# Gesture.net
KiCad netlist of a schematic drawn in EAGLE
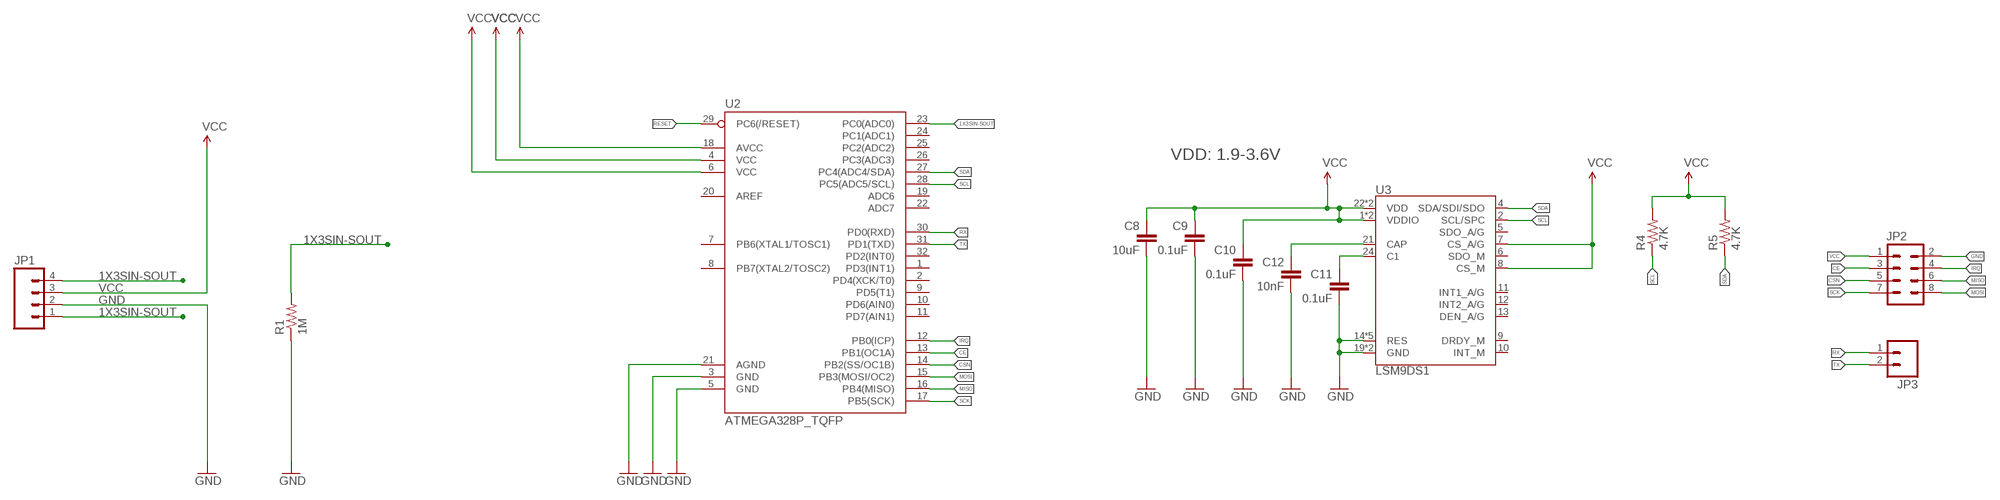
[diagram p0: schematic, sheet 1]

(export (version "E")
  (design (tool "Eeschema 10.0.6"))
  (components
    (comp (ref "C8")
      (value "10uF")
      (footprint "eagle-import:0603-CAP")
      (libsource (lib "eagle-import") (part "10UF-6.3V-20%(0603)"))
    )
    (comp (ref "C9")
      (value "0.1uF")
      (footprint "eagle-import:0603-CAP")
      (libsource (lib "eagle-import") (part "0.1UF-25V(+80/-20%)(0603)"))
    )
    (comp (ref "C10")
      (value "0.1uF")
      (footprint "eagle-import:0603-CAP")
      (libsource (lib "eagle-import") (part "0.1UF-25V(+80/-20%)(0603)"))
    )
    (comp (ref "C11")
      (value "0.1uF")
      (footprint "eagle-import:0603-CAP")
      (libsource (lib "eagle-import") (part "0.1UF-25V(+80/-20%)(0603)"))
    )
    (comp (ref "C12")
      (value "10nF")
      (footprint "eagle-import:0603-CAP")
      (libsource (lib "eagle-import") (part "10NF/10000PF-50V-10%(0603)"))
    )
    (comp (ref "JP1")
      (value "M04PTH")
      (footprint "eagle-import:1X04")
      (libsource (lib "eagle-import") (part "M04PTH"))
    )
    (comp (ref "JP2")
      (value "M04X2_0.05\"")
      (footprint "eagle-import:M04X2_0.05_")
      (libsource (lib "eagle-import") (part "M04X2_0.05{dblquote}"))
    )
    (comp (ref "JP3")
      (value "M02LOCK")
      (footprint "eagle-import:1X02_LOCK")
      (libsource (lib "eagle-import") (part "M02LOCK"))
    )
    (comp (ref "R1")
      (value "1M")
      (footprint "eagle-import:R0603")
      (libsource (lib "eagle-import") (part "R-US_R0603"))
    )
    (comp (ref "R4")
      (value "4.7K")
      (footprint "eagle-import:0603-RES")
      (libsource (lib "eagle-import") (part "4.7KOHM-1/10W-1%(0603)"))
    )
    (comp (ref "R5")
      (value "4.7K")
      (footprint "eagle-import:0603-RES")
      (libsource (lib "eagle-import") (part "4.7KOHM-1/10W-1%(0603)"))
    )
    (comp (ref "U2")
      (value "ATMEGA328P_TQFP")
      (footprint "eagle-import:TQFP32-08")
      (libsource (lib "eagle-import") (part "ATMEGA328P_TQFP"))
    )
    (comp (ref "U3")
      (value "LSM9DS1")
      (footprint "eagle-import:LGA24-8X4")
      (libsource (lib "eagle-import") (part "LSM9DS1"))
    )
  )
  (nets
    (net (code "1") (name "1X3SIN-SOUT") (class "Default")
      (node (ref "JP1") (pin "1") (pinfunction "1_1") (pintype "passive"))
      (node (ref "JP1") (pin "4") (pinfunction "4_4") (pintype "passive"))
      (node (ref "R1") (pin "2") (pinfunction "2_2") (pintype "passive"))
      (node (ref "U2") (pin "23") (pinfunction "PC0(ADC0)_23") (pintype "bidirectional"))
    )
    (net (code "2") (name "CE") (class "Default")
      (node (ref "JP2") (pin "3") (pinfunction "3_3") (pintype "passive"))
      (node (ref "U2") (pin "13") (pinfunction "PB1(OC1A)_13") (pintype "bidirectional"))
    )
    (net (code "3") (name "CSN") (class "Default")
      (node (ref "JP2") (pin "5") (pinfunction "5_5") (pintype "passive"))
      (node (ref "U2") (pin "14") (pinfunction "PB2(SS/OC1B)_14") (pintype "bidirectional"))
    )
    (net (code "4") (name "GND") (class "Default")
      (node (ref "C10") (pin "2") (pinfunction "2_2") (pintype "passive"))
      (node (ref "C11") (pin "2") (pinfunction "2_2") (pintype "passive"))
      (node (ref "C12") (pin "2") (pinfunction "2_2") (pintype "passive"))
      (node (ref "C8") (pin "2") (pinfunction "2_2") (pintype "passive"))
      (node (ref "C9") (pin "2") (pinfunction "2_2") (pintype "passive"))
      (node (ref "JP1") (pin "2") (pinfunction "2_2") (pintype "passive"))
      (node (ref "JP2") (pin "2") (pinfunction "2_2") (pintype "passive"))
      (node (ref "R1") (pin "1") (pinfunction "1_1") (pintype "passive"))
      (node (ref "U2") (pin "21") (pinfunction "AGND_21") (pintype "bidirectional"))
      (node (ref "U2") (pin "3") (pinfunction "GND_3") (pintype "bidirectional"))
      (node (ref "U2") (pin "5") (pinfunction "GND_5") (pintype "bidirectional"))
      (node (ref "U3") (pin "14") (pinfunction "RES_14") (pintype "bidirectional"))
      (node (ref "U3") (pin "15") (pinfunction "RES_15") (pintype "bidirectional"))
      (node (ref "U3") (pin "16") (pinfunction "RES_16") (pintype "bidirectional"))
      (node (ref "U3") (pin "17") (pinfunction "RES_17") (pintype "bidirectional"))
      (node (ref "U3") (pin "18") (pinfunction "RES_18") (pintype "bidirectional"))
      (node (ref "U3") (pin "19") (pinfunction "GND_19") (pintype "bidirectional"))
      (node (ref "U3") (pin "20") (pinfunction "GND_20") (pintype "bidirectional"))
    )
    (net (code "5") (name "IRQ") (class "Default")
      (node (ref "JP2") (pin "4") (pinfunction "4_4") (pintype "passive"))
      (node (ref "U2") (pin "12") (pinfunction "PB0(ICP)_12") (pintype "bidirectional"))
    )
    (net (code "6") (name "MISO") (class "Default")
      (node (ref "JP2") (pin "6") (pinfunction "6_6") (pintype "passive"))
      (node (ref "U2") (pin "16") (pinfunction "PB4(MISO)_16") (pintype "bidirectional"))
    )
    (net (code "7") (name "MOSI") (class "Default")
      (node (ref "JP2") (pin "8") (pinfunction "8_8") (pintype "passive"))
      (node (ref "U2") (pin "15") (pinfunction "PB3(MOSI/OC2)_15") (pintype "bidirectional"))
    )
    (net (code "8") (name "Net-(U3-C1)") (class "Default")
      (node (ref "C11") (pin "1") (pinfunction "1_1") (pintype "passive"))
      (node (ref "U3") (pin "24") (pinfunction "C1_24") (pintype "bidirectional"))
    )
    (net (code "9") (name "Net-(U3-CAP)") (class "Default")
      (node (ref "C12") (pin "1") (pinfunction "1_1") (pintype "passive"))
      (node (ref "U3") (pin "21") (pinfunction "CAP_21") (pintype "bidirectional"))
    )
    (net (code "10") (name "RESET") (class "Default")
      (node (ref "U2") (pin "29") (pinfunction "PC6(/RESET)_29") (pintype "bidirectional"))
    )
    (net (code "11") (name "RX") (class "Default")
      (node (ref "JP3") (pin "1") (pinfunction "1_1") (pintype "passive"))
      (node (ref "U2") (pin "30") (pinfunction "PD0(RXD)_30") (pintype "bidirectional"))
    )
    (net (code "12") (name "SCK") (class "Default")
      (node (ref "JP2") (pin "7") (pinfunction "7_7") (pintype "passive"))
      (node (ref "U2") (pin "17") (pinfunction "PB5(SCK)_17") (pintype "bidirectional"))
    )
    (net (code "13") (name "SCL") (class "Default")
      (node (ref "R4") (pin "1") (pinfunction "1_1") (pintype "passive"))
      (node (ref "U2") (pin "28") (pinfunction "PC5(ADC5/SCL)_28") (pintype "bidirectional"))
      (node (ref "U3") (pin "2") (pinfunction "SCL/SPC_2") (pintype "bidirectional"))
    )
    (net (code "14") (name "SDA") (class "Default")
      (node (ref "R5") (pin "1") (pinfunction "1_1") (pintype "passive"))
      (node (ref "U2") (pin "27") (pinfunction "PC4(ADC4/SDA)_27") (pintype "bidirectional"))
      (node (ref "U3") (pin "4") (pinfunction "SDA/SDI/SDO_4") (pintype "bidirectional"))
    )
    (net (code "15") (name "TX") (class "Default")
      (node (ref "JP3") (pin "2") (pinfunction "2_2") (pintype "passive"))
      (node (ref "U2") (pin "31") (pinfunction "PD1(TXD)_31") (pintype "bidirectional"))
    )
    (net (code "16") (name "VCC") (class "Default")
      (node (ref "C10") (pin "1") (pinfunction "1_1") (pintype "passive"))
      (node (ref "C8") (pin "1") (pinfunction "1_1") (pintype "passive"))
      (node (ref "C9") (pin "1") (pinfunction "1_1") (pintype "passive"))
      (node (ref "JP1") (pin "3") (pinfunction "3_3") (pintype "passive"))
      (node (ref "JP2") (pin "1") (pinfunction "1_1") (pintype "passive"))
      (node (ref "R4") (pin "2") (pinfunction "2_2") (pintype "passive"))
      (node (ref "R5") (pin "2") (pinfunction "2_2") (pintype "passive"))
      (node (ref "U2") (pin "18") (pinfunction "AVCC_18") (pintype "bidirectional"))
      (node (ref "U2") (pin "4") (pinfunction "VCC_4") (pintype "bidirectional"))
      (node (ref "U2") (pin "6") (pinfunction "VCC_6") (pintype "bidirectional"))
      (node (ref "U3") (pin "1") (pinfunction "VDDIO_1") (pintype "bidirectional"))
      (node (ref "U3") (pin "22") (pinfunction "VDD_22") (pintype "bidirectional"))
      (node (ref "U3") (pin "23") (pinfunction "VDD_23") (pintype "bidirectional"))
      (node (ref "U3") (pin "3") (pinfunction "VDDIO_3") (pintype "bidirectional"))
      (node (ref "U3") (pin "7") (pinfunction "CS_A/G_7") (pintype "bidirectional"))
      (node (ref "U3") (pin "8") (pinfunction "CS_M_8") (pintype "bidirectional"))
    )
    (net (code "17") (name "unconnected-(U2-ADC6-Pad19)") (class "Default")
      (node (ref "U2") (pin "19") (pinfunction "ADC6_19") (pintype "bidirectional"))
    )
    (net (code "18") (name "unconnected-(U2-ADC7-Pad22)") (class "Default")
      (node (ref "U2") (pin "22") (pinfunction "ADC7_22") (pintype "bidirectional"))
    )
    (net (code "19") (name "unconnected-(U2-AREF-Pad20)") (class "Default")
      (node (ref "U2") (pin "20") (pinfunction "AREF_20") (pintype "bidirectional"))
    )
    (net (code "20") (name "unconnected-(U2-PB6(XTAL1{slash}TOSC1)-Pad7)") (class "Default")
      (node (ref "U2") (pin "7") (pinfunction "PB6(XTAL1/TOSC1)_7") (pintype "bidirectional"))
    )
    (net (code "21") (name "unconnected-(U2-PB7(XTAL2{slash}TOSC2)-Pad8)") (class "Default")
      (node (ref "U2") (pin "8") (pinfunction "PB7(XTAL2/TOSC2)_8") (pintype "bidirectional"))
    )
    (net (code "22") (name "unconnected-(U2-PC1(ADC1)-Pad24)") (class "Default")
      (node (ref "U2") (pin "24") (pinfunction "PC1(ADC1)_24") (pintype "bidirectional"))
    )
    (net (code "23") (name "unconnected-(U2-PC2(ADC2)-Pad25)") (class "Default")
      (node (ref "U2") (pin "25") (pinfunction "PC2(ADC2)_25") (pintype "bidirectional"))
    )
    (net (code "24") (name "unconnected-(U2-PC3(ADC3)-Pad26)") (class "Default")
      (node (ref "U2") (pin "26") (pinfunction "PC3(ADC3)_26") (pintype "bidirectional"))
    )
    (net (code "25") (name "unconnected-(U2-PD2(INT0)-Pad32)") (class "Default")
      (node (ref "U2") (pin "32") (pinfunction "PD2(INT0)_32") (pintype "bidirectional"))
    )
    (net (code "26") (name "unconnected-(U2-PD3(INT1)-Pad1)") (class "Default")
      (node (ref "U2") (pin "1") (pinfunction "PD3(INT1)_1") (pintype "bidirectional"))
    )
    (net (code "27") (name "unconnected-(U2-PD4(XCK{slash}T0)-Pad2)") (class "Default")
      (node (ref "U2") (pin "2") (pinfunction "PD4(XCK/T0)_2") (pintype "bidirectional"))
    )
    (net (code "28") (name "unconnected-(U2-PD5(T1)-Pad9)") (class "Default")
      (node (ref "U2") (pin "9") (pinfunction "PD5(T1)_9") (pintype "bidirectional"))
    )
    (net (code "29") (name "unconnected-(U2-PD6(AIN0)-Pad10)") (class "Default")
      (node (ref "U2") (pin "10") (pinfunction "PD6(AIN0)_10") (pintype "bidirectional"))
    )
    (net (code "30") (name "unconnected-(U2-PD7(AIN1)-Pad11)") (class "Default")
      (node (ref "U2") (pin "11") (pinfunction "PD7(AIN1)_11") (pintype "bidirectional"))
    )
    (net (code "31") (name "unconnected-(U3-DEN_A{slash}G-Pad13)") (class "Default")
      (node (ref "U3") (pin "13") (pinfunction "DEN_A/G_13") (pintype "bidirectional"))
    )
    (net (code "32") (name "unconnected-(U3-DRDY_M-Pad9)") (class "Default")
      (node (ref "U3") (pin "9") (pinfunction "DRDY_M_9") (pintype "bidirectional"))
    )
    (net (code "33") (name "unconnected-(U3-INT1_A{slash}G-Pad11)") (class "Default")
      (node (ref "U3") (pin "11") (pinfunction "INT1_A/G_11") (pintype "bidirectional"))
    )
    (net (code "34") (name "unconnected-(U3-INT2_A{slash}G-Pad12)") (class "Default")
      (node (ref "U3") (pin "12") (pinfunction "INT2_A/G_12") (pintype "bidirectional"))
    )
    (net (code "35") (name "unconnected-(U3-INT_M-Pad10)") (class "Default")
      (node (ref "U3") (pin "10") (pinfunction "INT_M_10") (pintype "bidirectional"))
    )
    (net (code "36") (name "unconnected-(U3-SDO_A{slash}G-Pad5)") (class "Default")
      (node (ref "U3") (pin "5") (pinfunction "SDO_A/G_5") (pintype "bidirectional"))
    )
    (net (code "37") (name "unconnected-(U3-SDO_M-Pad6)") (class "Default")
      (node (ref "U3") (pin "6") (pinfunction "SDO_M_6") (pintype "bidirectional"))
    )
  )
)
